# Acceleration.net
KiCad netlist of a schematic drawn in EAGLE
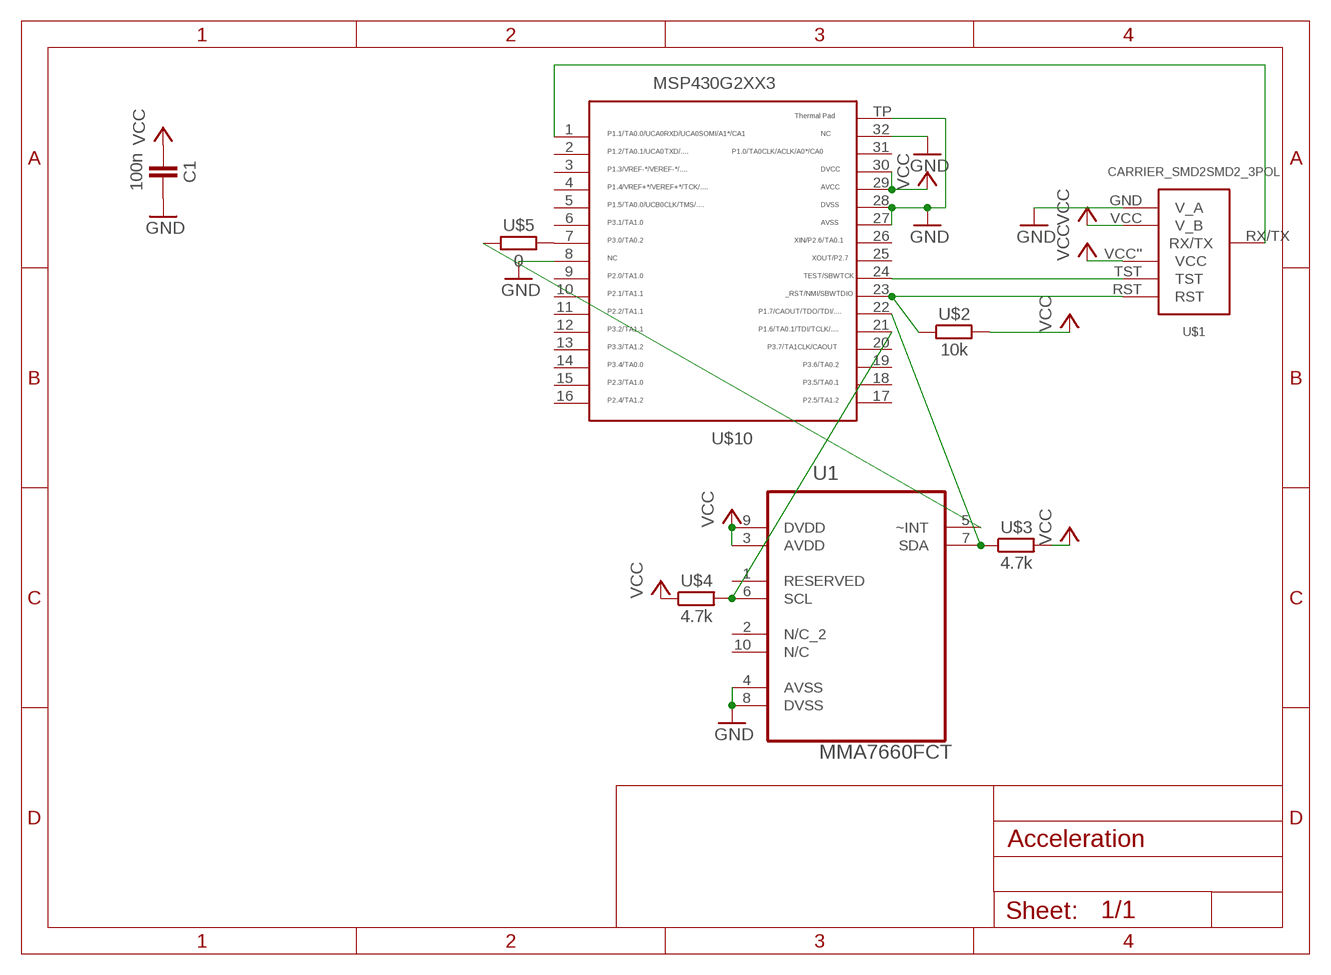
[diagram p0: schematic, sheet 1]

(export (version "E")
  (design (tool "Eeschema 10.0.6"))
  (components
    (comp (ref "C1")
      (value "100n")
      (footprint "eagle-import:603")
      (libsource (lib "eagle-import") (part "CAPACITOR"))
    )
    (comp (ref "U$1")
      (value "CARRIER_SMD2SMD2_3POL")
      (footprint "eagle-import:CARRIER_SMD2_3POL")
      (libsource (lib "eagle-import") (part "CARRIER_SMD2SMD2_3POL"))
    )
    (comp (ref "U$2")
      (value "10k")
      (footprint "eagle-import:603")
      (libsource (lib "eagle-import") (part "RESISTOR0603"))
    )
    (comp (ref "U$3")
      (value "4.7k")
      (footprint "eagle-import:603")
      (libsource (lib "eagle-import") (part "RESISTOR0603"))
    )
    (comp (ref "U$4")
      (value "4.7k")
      (footprint "eagle-import:603")
      (libsource (lib "eagle-import") (part "RESISTOR0603"))
    )
    (comp (ref "U$5")
      (value "0")
      (footprint "eagle-import:1206")
      (libsource (lib "eagle-import") (part "RESISTOR1206"))
    )
    (comp (ref "U$10")
      (value "MSP430G2553")
      (footprint "eagle-import:QFN32")
      (libsource (lib "eagle-import") (part "MSP430G2553"))
    )
    (comp (ref "U1")
      (value "MMA7660FCT")
      (footprint "eagle-import:DFN300X300X100-10N")
      (libsource (lib "eagle-import") (part "MMA7660FCT"))
    )
  )
  (nets
    (net (code "1") (name "GND") (class "Default")
      (node (ref "C1") (pin "2") (pinfunction "2_2") (pintype "passive"))
      (node (ref "U$1") (pin "GND") (pinfunction "V_A_GND") (pintype "bidirectional"))
      (node (ref "U$10") (pin "27") (pinfunction "27_27") (pintype "bidirectional"))
      (node (ref "U$10") (pin "28") (pinfunction "28_28") (pintype "bidirectional"))
      (node (ref "U$10") (pin "32") (pinfunction "32_32") (pintype "bidirectional"))
      (node (ref "U$10") (pin "8") (pinfunction "8_8") (pintype "bidirectional"))
      (node (ref "U$10") (pin "TP") (pinfunction "TP_TP") (pintype "bidirectional"))
      (node (ref "U1") (pin "4") (pinfunction "AVSS_4") (pintype "power_in"))
      (node (ref "U1") (pin "8") (pinfunction "DVSS_8") (pintype "power_in"))
    )
    (net (code "2") (name "Net-(U$1-PadRST)") (class "Default")
      (node (ref "U$1") (pin "RST") (pinfunction "RST_RST") (pintype "bidirectional"))
      (node (ref "U$10") (pin "23") (pinfunction "23_23") (pintype "bidirectional"))
      (node (ref "U$2") (pin "1") (pinfunction "1_1") (pintype "passive"))
    )
    (net (code "3") (name "Net-(U$1-PadRX{slash}TX)") (class "Default")
      (node (ref "U$1") (pin "RX/TX") (pinfunction "RX/TX_RX/TX") (pintype "bidirectional"))
      (node (ref "U$10") (pin "1") (pinfunction "1_1") (pintype "bidirectional"))
    )
    (net (code "4") (name "Net-(U$1-PadTST)") (class "Default")
      (node (ref "U$1") (pin "TST") (pinfunction "TST_TST") (pintype "bidirectional"))
      (node (ref "U$10") (pin "24") (pinfunction "24_24") (pintype "bidirectional"))
    )
    (net (code "5") (name "Net-(U$10-Pad7)") (class "Default")
      (node (ref "U$10") (pin "7") (pinfunction "7_7") (pintype "bidirectional"))
      (node (ref "U$5") (pin "2") (pinfunction "2_2") (pintype "passive"))
    )
    (net (code "6") (name "Net-(U1-SCL)") (class "Default")
      (node (ref "U$10") (pin "21") (pinfunction "21_21") (pintype "bidirectional"))
      (node (ref "U$4") (pin "2") (pinfunction "2_2") (pintype "passive"))
      (node (ref "U1") (pin "6") (pinfunction "SCL_6") (pintype "input"))
    )
    (net (code "7") (name "Net-(U1-SDA)") (class "Default")
      (node (ref "U$10") (pin "22") (pinfunction "22_22") (pintype "bidirectional"))
      (node (ref "U$3") (pin "1") (pinfunction "1_1") (pintype "passive"))
      (node (ref "U1") (pin "7") (pinfunction "SDA_7") (pintype "bidirectional"))
    )
    (net (code "8") (name "Net-(U1-~{INT})") (class "Default")
      (node (ref "U$5") (pin "1") (pinfunction "1_1") (pintype "passive"))
      (node (ref "U1") (pin "5") (pinfunction "~{INT}_5") (pintype "output"))
    )
    (net (code "9") (name "VCC") (class "Default")
      (node (ref "C1") (pin "1") (pinfunction "1_1") (pintype "passive"))
      (node (ref "U$1") (pin "VCC") (pinfunction "V_B_VCC") (pintype "bidirectional"))
      (node (ref "U$1") (pin "VCC''") (pinfunction "VCC_VCC''") (pintype "bidirectional"))
      (node (ref "U$10") (pin "29") (pinfunction "29_29") (pintype "bidirectional"))
      (node (ref "U$10") (pin "30") (pinfunction "30_30") (pintype "bidirectional"))
      (node (ref "U$2") (pin "2") (pinfunction "2_2") (pintype "passive"))
      (node (ref "U$3") (pin "2") (pinfunction "2_2") (pintype "passive"))
      (node (ref "U$4") (pin "1") (pinfunction "1_1") (pintype "passive"))
      (node (ref "U1") (pin "3") (pinfunction "AVDD_3") (pintype "power_in"))
      (node (ref "U1") (pin "9") (pinfunction "DVDD_9") (pintype "power_in"))
    )
    (net (code "10") (name "unconnected-(U$10-Pad2)") (class "Default")
      (node (ref "U$10") (pin "2") (pinfunction "2_2") (pintype "bidirectional"))
    )
    (net (code "11") (name "unconnected-(U$10-Pad3)") (class "Default")
      (node (ref "U$10") (pin "3") (pinfunction "3_3") (pintype "bidirectional"))
    )
    (net (code "12") (name "unconnected-(U$10-Pad4)") (class "Default")
      (node (ref "U$10") (pin "4") (pinfunction "4_4") (pintype "bidirectional"))
    )
    (net (code "13") (name "unconnected-(U$10-Pad5)") (class "Default")
      (node (ref "U$10") (pin "5") (pinfunction "5_5") (pintype "bidirectional"))
    )
    (net (code "14") (name "unconnected-(U$10-Pad6)") (class "Default")
      (node (ref "U$10") (pin "6") (pinfunction "6_6") (pintype "bidirectional"))
    )
    (net (code "15") (name "unconnected-(U$10-Pad9)") (class "Default")
      (node (ref "U$10") (pin "9") (pinfunction "9_9") (pintype "bidirectional"))
    )
    (net (code "16") (name "unconnected-(U$10-Pad10)") (class "Default")
      (node (ref "U$10") (pin "10") (pinfunction "10_10") (pintype "bidirectional"))
    )
    (net (code "17") (name "unconnected-(U$10-Pad11)") (class "Default")
      (node (ref "U$10") (pin "11") (pinfunction "11_11") (pintype "bidirectional"))
    )
    (net (code "18") (name "unconnected-(U$10-Pad12)") (class "Default")
      (node (ref "U$10") (pin "12") (pinfunction "12_12") (pintype "bidirectional"))
    )
    (net (code "19") (name "unconnected-(U$10-Pad13)") (class "Default")
      (node (ref "U$10") (pin "13") (pinfunction "13_13") (pintype "bidirectional"))
    )
    (net (code "20") (name "unconnected-(U$10-Pad14)") (class "Default")
      (node (ref "U$10") (pin "14") (pinfunction "14_14") (pintype "bidirectional"))
    )
    (net (code "21") (name "unconnected-(U$10-Pad15)") (class "Default")
      (node (ref "U$10") (pin "15") (pinfunction "15_15") (pintype "bidirectional"))
    )
    (net (code "22") (name "unconnected-(U$10-Pad16)") (class "Default")
      (node (ref "U$10") (pin "16") (pinfunction "16_16") (pintype "bidirectional"))
    )
    (net (code "23") (name "unconnected-(U$10-Pad17)") (class "Default")
      (node (ref "U$10") (pin "17") (pinfunction "17_17") (pintype "bidirectional"))
    )
    (net (code "24") (name "unconnected-(U$10-Pad18)") (class "Default")
      (node (ref "U$10") (pin "18") (pinfunction "18_18") (pintype "bidirectional"))
    )
    (net (code "25") (name "unconnected-(U$10-Pad19)") (class "Default")
      (node (ref "U$10") (pin "19") (pinfunction "19_19") (pintype "bidirectional"))
    )
    (net (code "26") (name "unconnected-(U$10-Pad20)") (class "Default")
      (node (ref "U$10") (pin "20") (pinfunction "20_20") (pintype "bidirectional"))
    )
    (net (code "27") (name "unconnected-(U$10-Pad25)") (class "Default")
      (node (ref "U$10") (pin "25") (pinfunction "25_25") (pintype "bidirectional"))
    )
    (net (code "28") (name "unconnected-(U$10-Pad26)") (class "Default")
      (node (ref "U$10") (pin "26") (pinfunction "26_26") (pintype "bidirectional"))
    )
    (net (code "29") (name "unconnected-(U$10-Pad31)") (class "Default")
      (node (ref "U$10") (pin "31") (pinfunction "31_31") (pintype "bidirectional"))
    )
    (net (code "30") (name "unconnected-(U1-N{slash}C-Pad10)") (class "Default")
      (node (ref "U1") (pin "10") (pinfunction "N/C_10") (pintype "no_connect"))
    )
    (net (code "31") (name "unconnected-(U1-N{slash}C_2-Pad2)") (class "Default")
      (node (ref "U1") (pin "2") (pinfunction "N/C_2_2") (pintype "no_connect"))
    )
    (net (code "32") (name "unconnected-(U1-RESERVED-Pad1)") (class "Default")
      (node (ref "U1") (pin "1") (pinfunction "RESERVED_1") (pintype "passive"))
    )
  )
)
